# kfly_v3_1.net
KiCad netlist of a schematic drawn in EAGLE
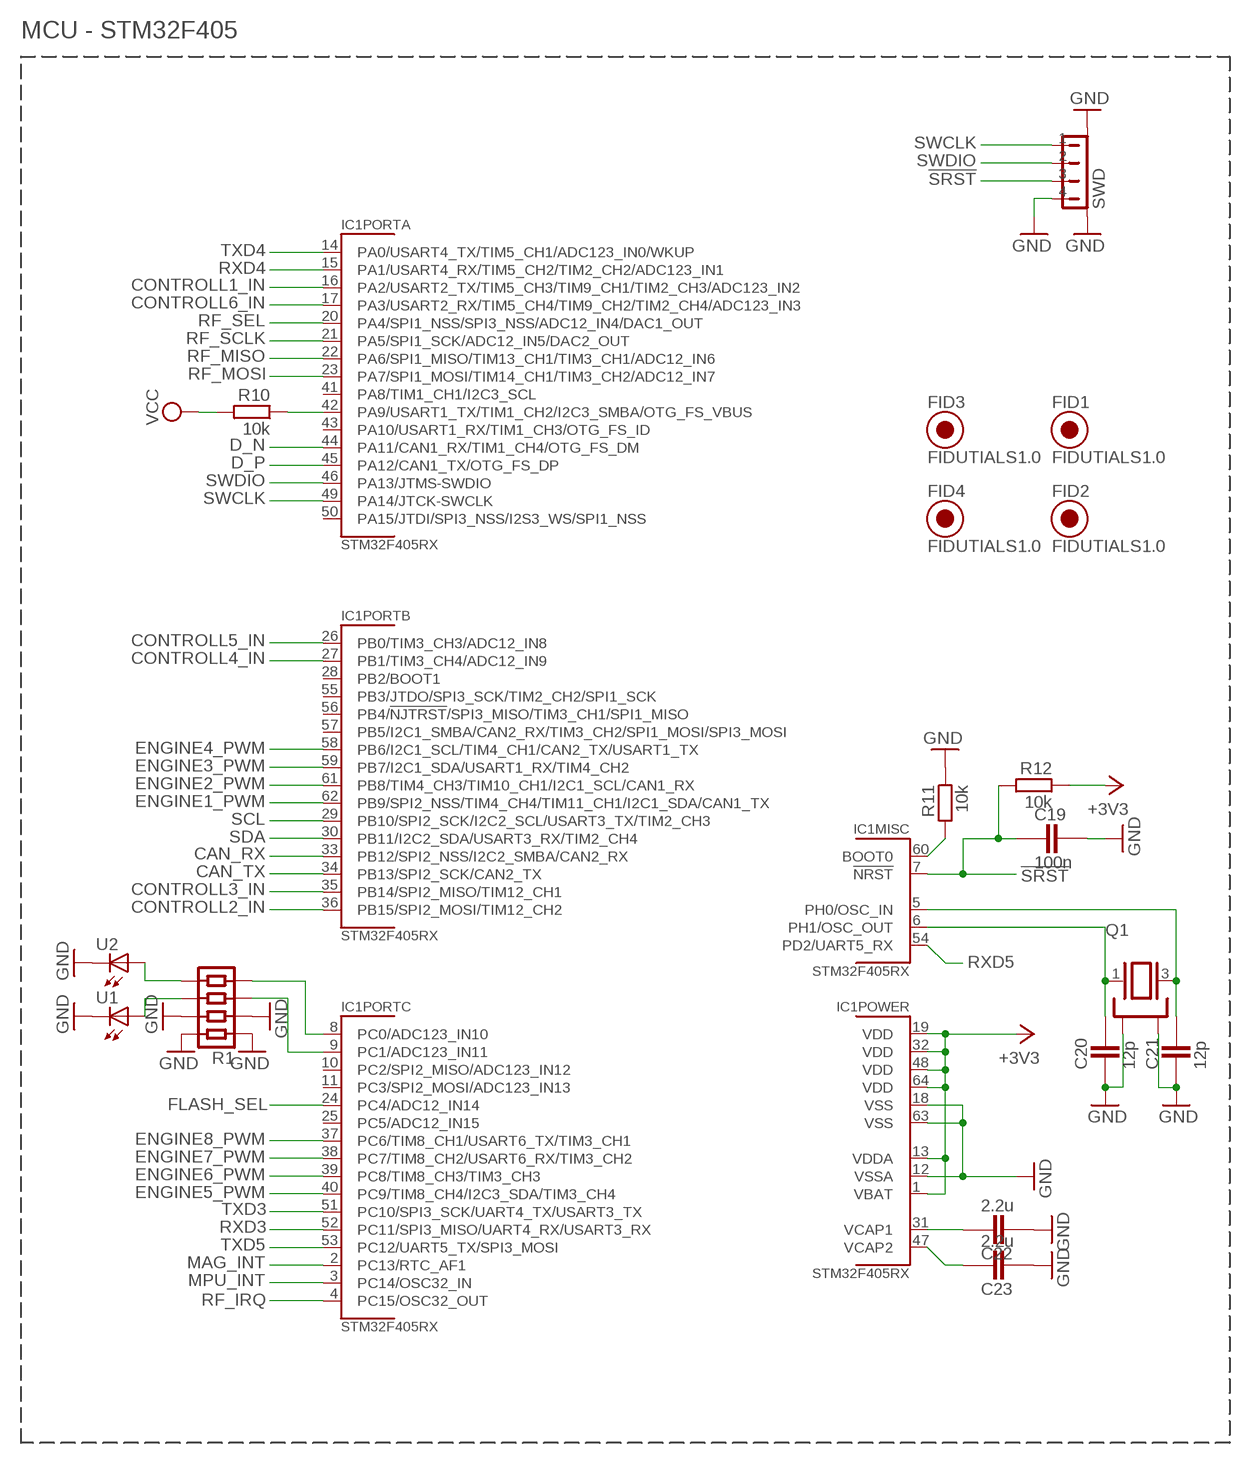
[diagram p0: schematic, sheet 1]
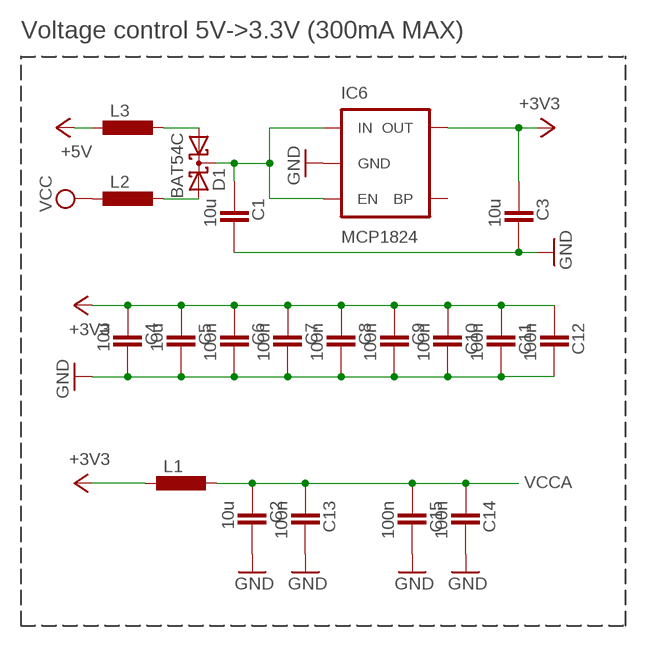
[diagram p1: schematic, sheet 2]
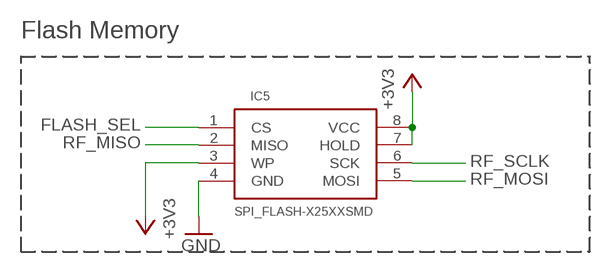
[diagram p2: schematic, sheet 3]
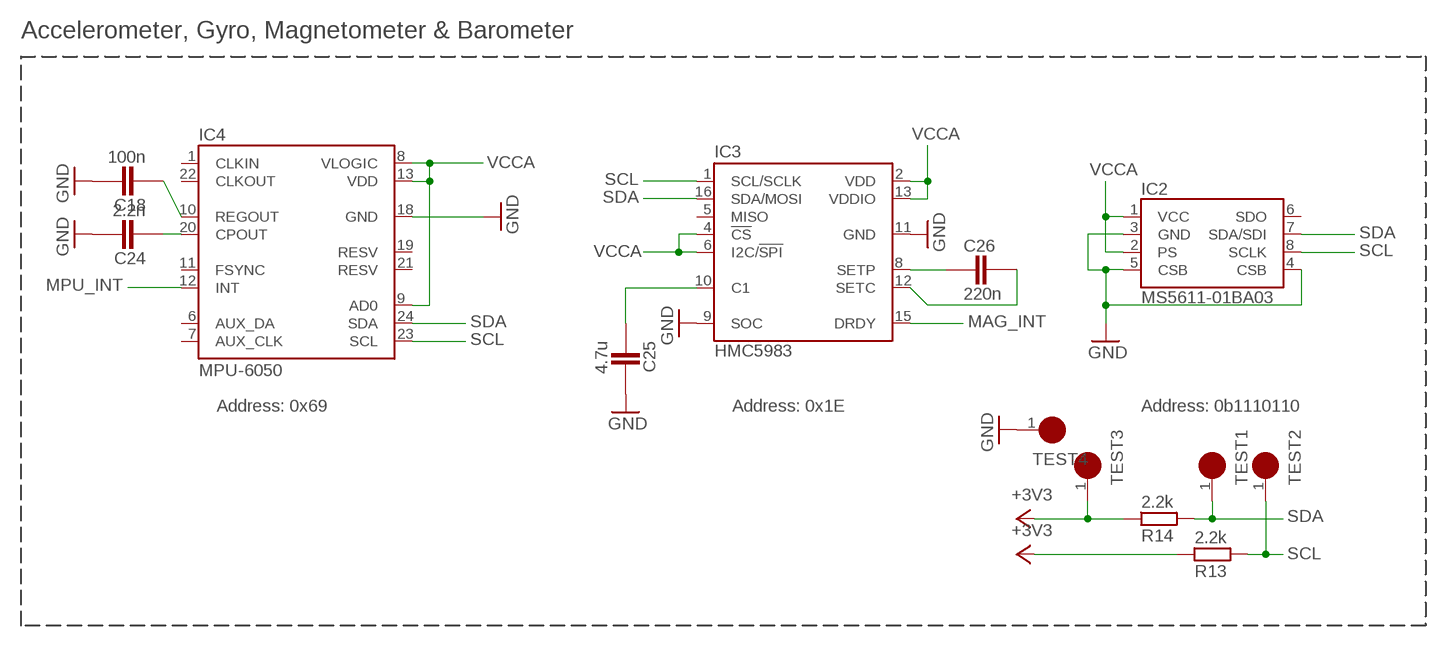
[diagram p3: schematic, sheet 4]
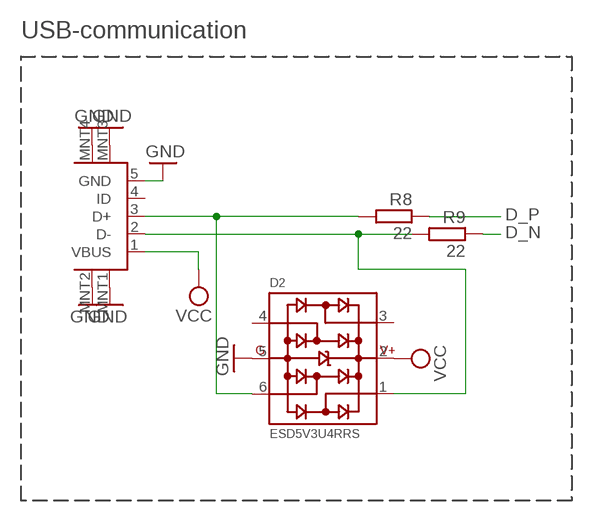
[diagram p4: schematic, sheet 5]
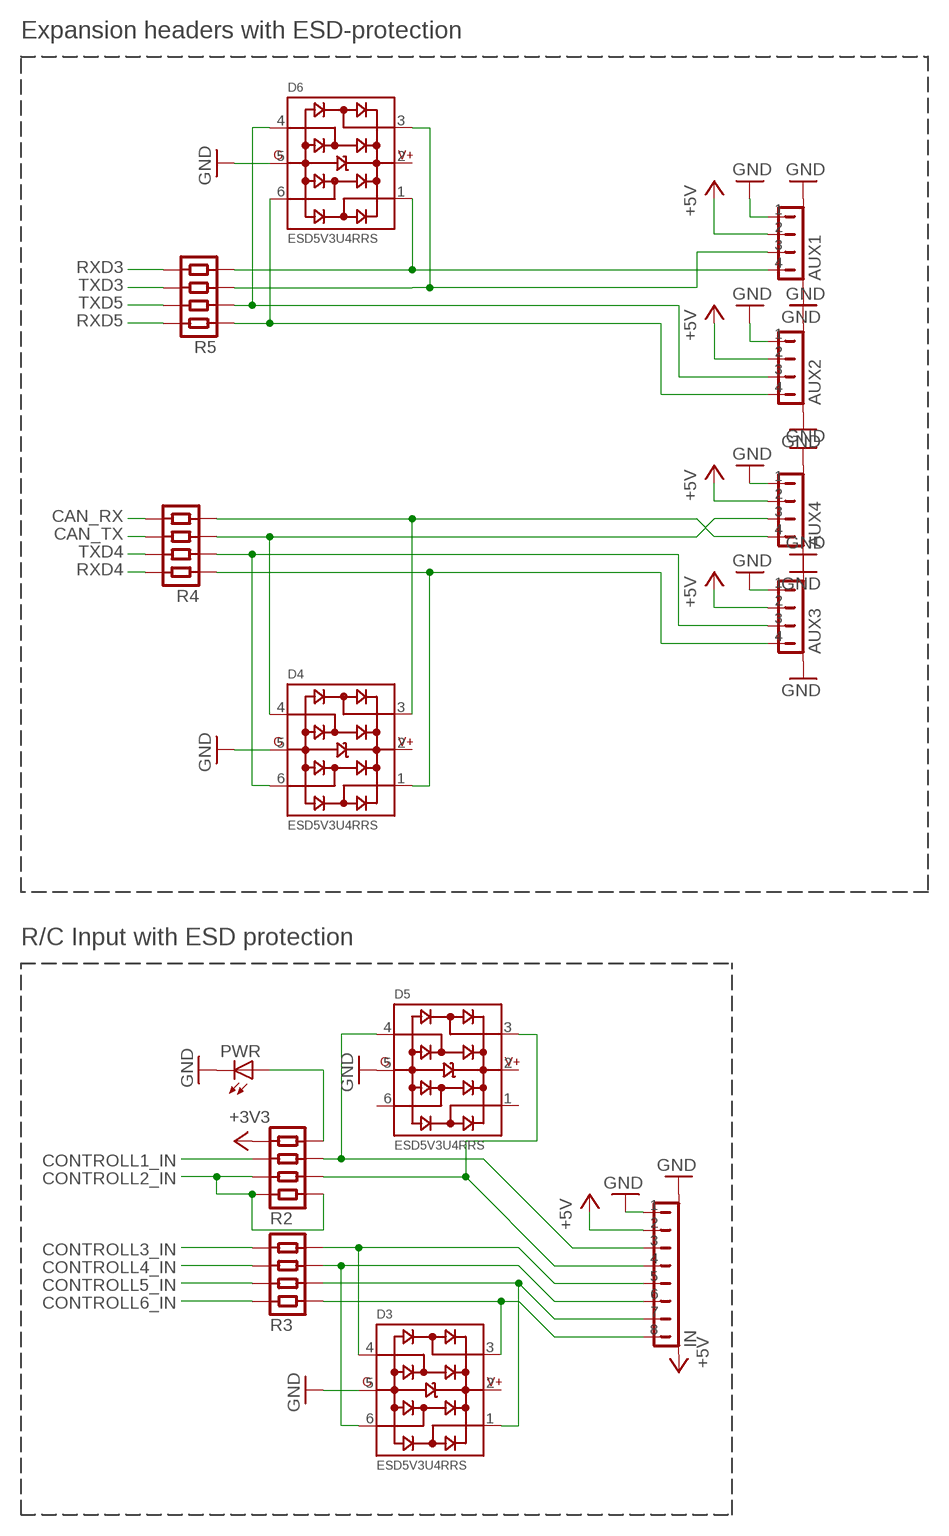
[diagram p5: schematic, sheet 6]
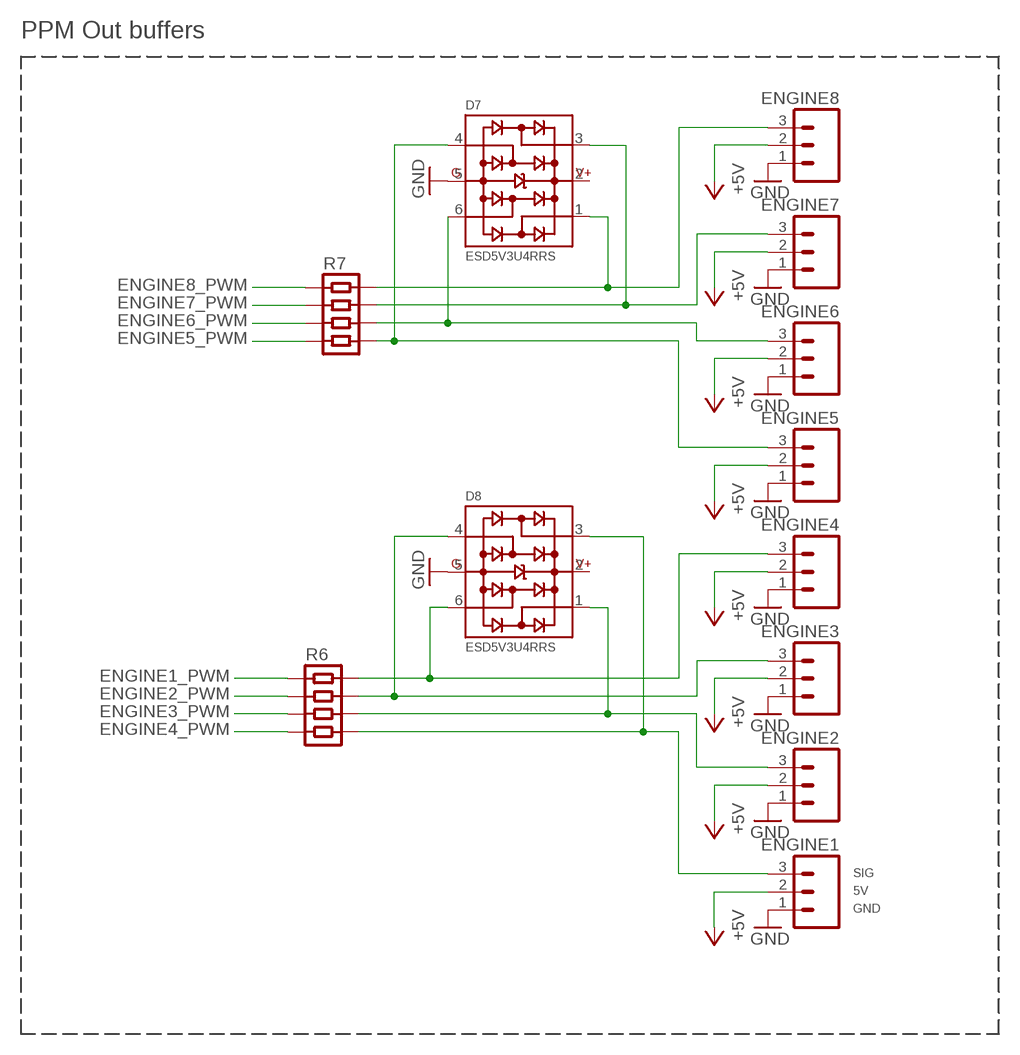
[diagram p6: schematic, sheet 7]
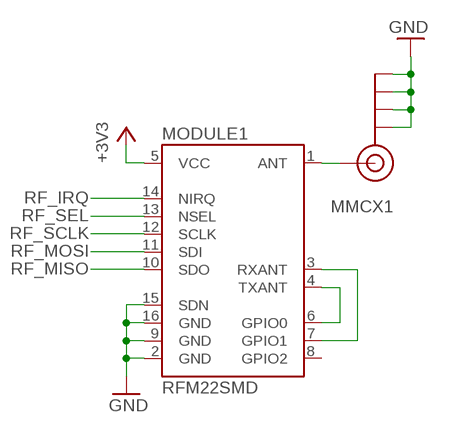
[diagram p7: schematic, sheet 8]

(export (version "E")
  (design (tool "Eeschema 10.0.6"))
  (components
    (comp (ref "C1")
      (value "10u")
      (footprint "eagle-import:CAPC1608X92N")
      (libsource (lib "eagle-import") (part "CAPACITOR_0603"))
    )
    (comp (ref "C2")
      (value "10u")
      (footprint "eagle-import:CAPC1608X92N")
      (libsource (lib "eagle-import") (part "CAPACITOR_0603"))
    )
    (comp (ref "C3")
      (value "10u")
      (footprint "eagle-import:CAPC1608X92N")
      (libsource (lib "eagle-import") (part "CAPACITOR_0603"))
    )
    (comp (ref "C4")
      (value "10u")
      (footprint "eagle-import:CAPC1608X92N")
      (libsource (lib "eagle-import") (part "CAPACITOR_0603"))
    )
    (comp (ref "C5")
      (value "10u")
      (footprint "eagle-import:CAPC1608X92N")
      (libsource (lib "eagle-import") (part "CAPACITOR_0603"))
    )
    (comp (ref "C6")
      (value "100n")
      (footprint "eagle-import:CAPC1005X60N")
      (libsource (lib "eagle-import") (part "CAPACITOR_0402"))
    )
    (comp (ref "C7")
      (value "100n")
      (footprint "eagle-import:CAPC1005X60N")
      (libsource (lib "eagle-import") (part "CAPACITOR_0402"))
    )
    (comp (ref "C8")
      (value "100n")
      (footprint "eagle-import:CAPC1005X60N")
      (libsource (lib "eagle-import") (part "CAPACITOR_0402"))
    )
    (comp (ref "C9")
      (value "100n")
      (footprint "eagle-import:CAPC1005X60N")
      (libsource (lib "eagle-import") (part "CAPACITOR_0402"))
    )
    (comp (ref "C10")
      (value "100n")
      (footprint "eagle-import:CAPC1005X60N")
      (libsource (lib "eagle-import") (part "CAPACITOR_0402"))
    )
    (comp (ref "C11")
      (value "100n")
      (footprint "eagle-import:CAPC1005X60N")
      (libsource (lib "eagle-import") (part "CAPACITOR_0402"))
    )
    (comp (ref "C12")
      (value "100n")
      (footprint "eagle-import:CAPC1005X60N")
      (libsource (lib "eagle-import") (part "CAPACITOR_0402"))
    )
    (comp (ref "C13")
      (value "100n")
      (footprint "eagle-import:CAPC1005X60N")
      (libsource (lib "eagle-import") (part "CAPACITOR_0402"))
    )
    (comp (ref "C14")
      (value "100n")
      (footprint "eagle-import:CAPC1005X60N")
      (libsource (lib "eagle-import") (part "CAPACITOR_0402"))
    )
    (comp (ref "C15")
      (value "100n")
      (footprint "eagle-import:CAPC1005X60N")
      (libsource (lib "eagle-import") (part "CAPACITOR_0402"))
    )
    (comp (ref "D1")
      (value "BAT54C")
      (footprint "eagle-import:SOT23")
      (libsource (lib "eagle-import") (part "BAT54C"))
    )
    (comp (ref "IC6")
      (value "MCP1824")
      (footprint "eagle-import:SOT23-5")
      (libsource (lib "eagle-import") (part "V_REG_LDOSMD"))
    )
    (comp (ref "L1")
      (value "INDUCTOR_0603")
      (footprint "eagle-import:INDC1608X95N")
      (libsource (lib "eagle-import") (part "INDUCTOR_0603"))
    )
    (comp (ref "L2")
      (value "INDUCTOR_0603")
      (footprint "eagle-import:INDC1608X95N")
      (libsource (lib "eagle-import") (part "INDUCTOR_0603"))
    )
    (comp (ref "L3")
      (value "INDUCTOR_0603")
      (footprint "eagle-import:INDC1608X95N")
      (libsource (lib "eagle-import") (part "INDUCTOR_0603"))
    )
    (comp (ref "C18")
      (value "100n")
      (footprint "eagle-import:CAPC1005X60N")
      (libsource (lib "eagle-import") (part "CAPACITOR_0402"))
    )
    (comp (ref "C24")
      (value "2.2n")
      (footprint "eagle-import:CAPC1005X60N")
      (libsource (lib "eagle-import") (part "CAPACITOR_0402"))
    )
    (comp (ref "C25")
      (value "4.7u")
      (footprint "eagle-import:CAPC1608X92N")
      (libsource (lib "eagle-import") (part "CAPACITOR_0603"))
    )
    (comp (ref "C26")
      (value "220n")
      (footprint "eagle-import:CAPC1608X92N")
      (libsource (lib "eagle-import") (part "CAPACITOR_0603"))
    )
    (comp (ref "IC2")
      (value "MS5611-01BA03")
      (footprint "eagle-import:MS5611")
      (libsource (lib "eagle-import") (part "MS5611-01BA01"))
    )
    (comp (ref "IC3")
      (value "HMC5983")
      (footprint "eagle-import:LPCC16")
      (libsource (lib "eagle-import") (part "HMC5983"))
    )
    (comp (ref "IC4")
      (value "MPU-6050")
      (footprint "eagle-import:QFN-24")
      (libsource (lib "eagle-import") (part "MPU-6050"))
    )
    (comp (ref "R13")
      (value "2.2k")
      (footprint "eagle-import:RESC1005X40AN")
      (libsource (lib "eagle-import") (part "RESISTOR_0402"))
    )
    (comp (ref "R14")
      (value "2.2k")
      (footprint "eagle-import:RESC1005X40AN")
      (libsource (lib "eagle-import") (part "RESISTOR_0402"))
    )
    (comp (ref "TEST1")
      (value "TESTPOINT")
      (footprint "eagle-import:TESTPOINT_1.2")
      (libsource (lib "eagle-import") (part "TESTPOINT"))
    )
    (comp (ref "TEST2")
      (value "TESTPOINT")
      (footprint "eagle-import:TESTPOINT_1.2")
      (libsource (lib "eagle-import") (part "TESTPOINT"))
    )
    (comp (ref "TEST3")
      (value "TESTPOINT")
      (footprint "eagle-import:TESTPOINT_1.2")
      (libsource (lib "eagle-import") (part "TESTPOINT"))
    )
    (comp (ref "TEST4")
      (value "TESTPOINT")
      (footprint "eagle-import:TESTPOINT_1.2")
      (libsource (lib "eagle-import") (part "TESTPOINT"))
    )
    (comp (ref "D7")
      (value "ESD5V3U4RRS")
      (footprint "eagle-import:SOT363")
      (libsource (lib "eagle-import") (part "ESD5V3U4RRS"))
    )
    (comp (ref "D8")
      (value "ESD5V3U4RRS")
      (footprint "eagle-import:SOT363")
      (libsource (lib "eagle-import") (part "ESD5V3U4RRS"))
    )
    (comp (ref "ENGINE1")
      (value "M03TH_90DEG")
      (footprint "eagle-import:M03_90DEG")
      (libsource (lib "eagle-import") (part "M03TH_90DEG"))
    )
    (comp (ref "ENGINE2")
      (value "M03TH_90DEG")
      (footprint "eagle-import:M03_90DEG")
      (libsource (lib "eagle-import") (part "M03TH_90DEG"))
    )
    (comp (ref "ENGINE3")
      (value "M03TH_90DEG")
      (footprint "eagle-import:M03_90DEG")
      (libsource (lib "eagle-import") (part "M03TH_90DEG"))
    )
    (comp (ref "ENGINE4")
      (value "M03TH_90DEG")
      (footprint "eagle-import:M03_90DEG")
      (libsource (lib "eagle-import") (part "M03TH_90DEG"))
    )
    (comp (ref "ENGINE5")
      (value "M03TH_90DEG")
      (footprint "eagle-import:M03_90DEG")
      (libsource (lib "eagle-import") (part "M03TH_90DEG"))
    )
    (comp (ref "ENGINE6")
      (value "M03TH_90DEG")
      (footprint "eagle-import:M03_90DEG")
      (libsource (lib "eagle-import") (part "M03TH_90DEG"))
    )
    (comp (ref "ENGINE7")
      (value "M03TH_90DEG")
      (footprint "eagle-import:M03_90DEG")
      (libsource (lib "eagle-import") (part "M03TH_90DEG"))
    )
    (comp (ref "ENGINE8")
      (value "M03TH_90DEG")
      (footprint "eagle-import:M03_90DEG")
      (libsource (lib "eagle-import") (part "M03TH_90DEG"))
    )
    (comp (ref "R6")
      (value "RESISTOR-4ARRAY-0804")
      (footprint "eagle-import:RESISTORARRAY_0804")
      (libsource (lib "eagle-import") (part "RESISTOR-4ARRAY-0804"))
    )
    (comp (ref "R7")
      (value "RESISTOR-4ARRAY-0804")
      (footprint "eagle-import:RESISTORARRAY_0804")
      (libsource (lib "eagle-import") (part "RESISTOR-4ARRAY-0804"))
    )
    (comp (ref "C19")
      (value "100n")
      (footprint "eagle-import:CAPC1005X60N")
      (libsource (lib "eagle-import") (part "CAPACITOR_0402"))
    )
    (comp (ref "C20")
      (value "12p")
      (footprint "eagle-import:CAPC1005X60N")
      (libsource (lib "eagle-import") (part "CAPACITOR_0402"))
    )
    (comp (ref "C21")
      (value "12p")
      (footprint "eagle-import:CAPC1005X60N")
      (libsource (lib "eagle-import") (part "CAPACITOR_0402"))
    )
    (comp (ref "C22")
      (value "2.2u")
      (footprint "eagle-import:CAPC1608X92N")
      (libsource (lib "eagle-import") (part "CAPACITOR_0603"))
    )
    (comp (ref "C23")
      (value "2.2u")
      (footprint "eagle-import:CAPC1608X92N")
      (libsource (lib "eagle-import") (part "CAPACITOR_0603"))
    )
    (comp (ref "FID1")
      (value "FIDUTIALS1.0")
      (footprint "eagle-import:FID1.0")
      (libsource (lib "eagle-import") (part "FIDUTIALS1.0"))
    )
    (comp (ref "FID2")
      (value "FIDUTIALS1.0")
      (footprint "eagle-import:FID1.0")
      (libsource (lib "eagle-import") (part "FIDUTIALS1.0"))
    )
    (comp (ref "FID3")
      (value "FIDUTIALS1.0")
      (footprint "eagle-import:FID1.0")
      (libsource (lib "eagle-import") (part "FIDUTIALS1.0"))
    )
    (comp (ref "FID4")
      (value "FIDUTIALS1.0")
      (footprint "eagle-import:FID1.0")
      (libsource (lib "eagle-import") (part "FIDUTIALS1.0"))
    )
    (comp (ref "IC1")
      (value "STM32F405RX")
      (footprint "eagle-import:LQFP64-10X10")
      (libsource (lib "eagle-import") (part "STM32F4X5RX"))
    )
    (comp (ref "Q1")
      (value "2.5X3.2CRYSTAL")
      (footprint "eagle-import:2.5X3.2CRYSTAL")
      (libsource (lib "eagle-import") (part "2.5X3.2CRYSTAL"))
    )
    (comp (ref "R1")
      (value "RESISTOR-4ARRAY-0804")
      (footprint "eagle-import:RESISTORARRAY_0804")
      (libsource (lib "eagle-import") (part "RESISTOR-4ARRAY-0804"))
    )
    (comp (ref "R10")
      (value "10k")
      (footprint "eagle-import:RESC1005X40AN")
      (libsource (lib "eagle-import") (part "RESISTOR_0402"))
    )
    (comp (ref "R11")
      (value "10k")
      (footprint "eagle-import:RESC1005X40AN")
      (libsource (lib "eagle-import") (part "RESISTOR_0402"))
    )
    (comp (ref "R12")
      (value "10k")
      (footprint "eagle-import:RESC1005X40AN")
      (libsource (lib "eagle-import") (part "RESISTOR_0402"))
    )
    (comp (ref "SWD")
      (value "JST-4PIN-SIDE-1.0")
      (footprint "eagle-import:JST-4PIN-SIDE")
      (libsource (lib "eagle-import") (part "JST-4PIN-SIDE-1.0"))
    )
    (comp (ref "U1")
      (value "LED0603")
      (footprint "eagle-import:LED-0603")
      (libsource (lib "eagle-import") (part "LED0603"))
    )
    (comp (ref "U2")
      (value "LED0603")
      (footprint "eagle-import:LED-0603")
      (libsource (lib "eagle-import") (part "LED0603"))
    )
    (comp (ref "AUX1")
      (value "JST-4PIN-SIDE-1.0")
      (footprint "eagle-import:JST-4PIN-SIDE")
      (libsource (lib "eagle-import") (part "JST-4PIN-SIDE-1.0"))
    )
    (comp (ref "AUX2")
      (value "JST-4PIN-SIDE-1.0")
      (footprint "eagle-import:JST-4PIN-SIDE")
      (libsource (lib "eagle-import") (part "JST-4PIN-SIDE-1.0"))
    )
    (comp (ref "AUX3")
      (value "JST-4PIN-SIDE-1.0")
      (footprint "eagle-import:JST-4PIN-SIDE")
      (libsource (lib "eagle-import") (part "JST-4PIN-SIDE-1.0"))
    )
    (comp (ref "AUX4")
      (value "JST-4PIN-SIDE-1.0")
      (footprint "eagle-import:JST-4PIN-SIDE")
      (libsource (lib "eagle-import") (part "JST-4PIN-SIDE-1.0"))
    )
    (comp (ref "D3")
      (value "ESD5V3U4RRS")
      (footprint "eagle-import:SOT363")
      (libsource (lib "eagle-import") (part "ESD5V3U4RRS"))
    )
    (comp (ref "D4")
      (value "ESD5V3U4RRS")
      (footprint "eagle-import:SOT363")
      (libsource (lib "eagle-import") (part "ESD5V3U4RRS"))
    )
    (comp (ref "D5")
      (value "ESD5V3U4RRS")
      (footprint "eagle-import:SOT363")
      (libsource (lib "eagle-import") (part "ESD5V3U4RRS"))
    )
    (comp (ref "D6")
      (value "ESD5V3U4RRS")
      (footprint "eagle-import:SOT363")
      (libsource (lib "eagle-import") (part "ESD5V3U4RRS"))
    )
    (comp (ref "IN")
      (value "JST-8PIN-SIDE-1.0")
      (footprint "eagle-import:JST-8PIN-SIDE")
      (libsource (lib "eagle-import") (part "JST-8PIN-SIDE-1.0"))
    )
    (comp (ref "PWR")
      (value "LED0603")
      (footprint "eagle-import:LED-0603")
      (libsource (lib "eagle-import") (part "LED0603"))
    )
    (comp (ref "R2")
      (value "RESISTOR-4ARRAY-0804")
      (footprint "eagle-import:RESISTORARRAY_0804")
      (libsource (lib "eagle-import") (part "RESISTOR-4ARRAY-0804"))
    )
    (comp (ref "R3")
      (value "RESISTOR-4ARRAY-0804")
      (footprint "eagle-import:RESISTORARRAY_0804")
      (libsource (lib "eagle-import") (part "RESISTOR-4ARRAY-0804"))
    )
    (comp (ref "R4")
      (value "RESISTOR-4ARRAY-0804")
      (footprint "eagle-import:RESISTORARRAY_0804")
      (libsource (lib "eagle-import") (part "RESISTOR-4ARRAY-0804"))
    )
    (comp (ref "R5")
      (value "RESISTOR-4ARRAY-0804")
      (footprint "eagle-import:RESISTORARRAY_0804")
      (libsource (lib "eagle-import") (part "RESISTOR-4ARRAY-0804"))
    )
    (comp (ref "IC5")
      (value "SPI_FLASH-X25XXSMD")
      (footprint "eagle-import:SO08")
      (libsource (lib "eagle-import") (part "SPI_FLASH-X25XXSMD"))
    )
    (comp (ref "D2")
      (value "ESD5V3U4RRS")
      (footprint "eagle-import:SOT363")
      (libsource (lib "eagle-import") (part "ESD5V3U4RRS"))
    )
    (comp (ref "R8")
      (value "22")
      (footprint "eagle-import:RESC1005X40AN")
      (libsource (lib "eagle-import") (part "RESISTOR_0402"))
    )
    (comp (ref "R9")
      (value "22")
      (footprint "eagle-import:RESC1005X40AN")
      (libsource (lib "eagle-import") (part "RESISTOR_0402"))
    )
    (comp (ref "USB1")
      (value "USB-MICRO-B-BOTTOM")
      (footprint "eagle-import:MICROUSB_TYPEB_SURFACE")
      (libsource (lib "eagle-import") (part "USB-MICRO-B-BOTTOM"))
    )
    (comp (ref "MMCX1")
      (value "MMCX")
      (footprint "eagle-import:MMCX_THROUGHHOLE_RIGHTANGLE")
      (libsource (lib "eagle-import") (part "MMCX"))
    )
    (comp (ref "MODULE1")
      (value "RFM22SMD")
      (footprint "eagle-import:RFM22-XXX-S2")
      (libsource (lib "eagle-import") (part "RFM22SMD"))
    )
  )
  (nets
    (net (code "1") (name "+3V3") (class "Default")
      (node (ref "C10") (pin "1") (pinfunction "1_1") (pintype "passive"))
      (node (ref "C11") (pin "1") (pinfunction "1_1") (pintype "passive"))
      (node (ref "C12") (pin "1") (pinfunction "1_1") (pintype "passive"))
      (node (ref "C3") (pin "1") (pinfunction "1_1") (pintype "passive"))
      (node (ref "C4") (pin "1") (pinfunction "1_1") (pintype "passive"))
      (node (ref "C5") (pin "1") (pinfunction "1_1") (pintype "passive"))
      (node (ref "C6") (pin "1") (pinfunction "1_1") (pintype "passive"))
      (node (ref "C7") (pin "1") (pinfunction "1_1") (pintype "passive"))
      (node (ref "C8") (pin "1") (pinfunction "1_1") (pintype "passive"))
      (node (ref "C9") (pin "1") (pinfunction "1_1") (pintype "passive"))
      (node (ref "IC1") (pin "1") (pinfunction "VBAT_1") (pintype "bidirectional"))
      (node (ref "IC1") (pin "13") (pinfunction "VDDA_13") (pintype "bidirectional"))
      (node (ref "IC1") (pin "19") (pinfunction "VDD_19") (pintype "bidirectional"))
      (node (ref "IC1") (pin "32") (pinfunction "VDD_32") (pintype "bidirectional"))
      (node (ref "IC1") (pin "48") (pinfunction "VDD_48") (pintype "bidirectional"))
      (node (ref "IC1") (pin "64") (pinfunction "VDD_64") (pintype "bidirectional"))
      (node (ref "IC5") (pin "3") (pinfunction "WP_3") (pintype "bidirectional"))
      (node (ref "IC5") (pin "7") (pinfunction "HOLD_7") (pintype "bidirectional"))
      (node (ref "IC5") (pin "8") (pinfunction "VCC_8") (pintype "bidirectional"))
      (node (ref "IC6") (pin "5") (pinfunction "OUT_5") (pintype "passive"))
      (node (ref "L1") (pin "1") (pinfunction "1_1") (pintype "passive"))
      (node (ref "MODULE1") (pin "5") (pinfunction "VCC_5") (pintype "bidirectional"))
      (node (ref "R12") (pin "1") (pinfunction "1_1") (pintype "passive"))
      (node (ref "R13") (pin "1") (pinfunction "1_1") (pintype "passive"))
      (node (ref "R14") (pin "1") (pinfunction "1_1") (pintype "passive"))
      (node (ref "R2") (pin "4") (pinfunction "4_4") (pintype "bidirectional"))
      (node (ref "TEST3") (pin "1") (pinfunction "2_1") (pintype "passive"))
    )
    (net (code "2") (name "+5V") (class "Default")
      (node (ref "AUX1") (pin "2") (pinfunction "2_2") (pintype "bidirectional"))
      (node (ref "AUX2") (pin "2") (pinfunction "2_2") (pintype "bidirectional"))
      (node (ref "AUX3") (pin "2") (pinfunction "2_2") (pintype "bidirectional"))
      (node (ref "AUX4") (pin "2") (pinfunction "2_2") (pintype "bidirectional"))
      (node (ref "ENGINE1") (pin "2") (pinfunction "2_2") (pintype "passive"))
      (node (ref "ENGINE2") (pin "2") (pinfunction "2_2") (pintype "passive"))
      (node (ref "ENGINE3") (pin "2") (pinfunction "2_2") (pintype "passive"))
      (node (ref "ENGINE4") (pin "2") (pinfunction "2_2") (pintype "passive"))
      (node (ref "ENGINE5") (pin "2") (pinfunction "2_2") (pintype "passive"))
      (node (ref "ENGINE6") (pin "2") (pinfunction "2_2") (pintype "passive"))
      (node (ref "ENGINE7") (pin "2") (pinfunction "2_2") (pintype "passive"))
      (node (ref "ENGINE8") (pin "2") (pinfunction "2_2") (pintype "passive"))
      (node (ref "IN") (pin "2") (pinfunction "2_2") (pintype "bidirectional"))
      (node (ref "IN") (pin "NC2") (pinfunction "GND2_NC2") (pintype "bidirectional"))
      (node (ref "L3") (pin "1") (pinfunction "1_1") (pintype "passive"))
    )
    (net (code "3") (name "CAN_RX") (class "Default")
      (node (ref "IC1") (pin "33") (pinfunction "PB12/SPI2_NSS/I2C2_SMBA/CAN2_RX_33") (pintype "bidirectional"))
      (node (ref "R4") (pin "5") (pinfunction "5_5") (pintype "bidirectional"))
    )
    (net (code "4") (name "CAN_TX") (class "Default")
      (node (ref "IC1") (pin "34") (pinfunction "PB13/SPI2_SCK/CAN2_TX_34") (pintype "bidirectional"))
      (node (ref "R4") (pin "6") (pinfunction "6_6") (pintype "bidirectional"))
    )
    (net (code "5") (name "CONTROLL1_IN") (class "Default")
      (node (ref "IC1") (pin "16") (pinfunction "PA2/USART2_TX/TIM5_CH3/TIM9_CH1/TIM2_CH3/ADC123_IN2_16") (pintype "bidirectional"))
      (node (ref "R2") (pin "3") (pinfunction "3_3") (pintype "bidirectional"))
    )
    (net (code "6") (name "CONTROLL2_IN") (class "Default")
      (node (ref "IC1") (pin "36") (pinfunction "PB15/SPI2_MOSI/TIM12_CH2_36") (pintype "bidirectional"))
      (node (ref "R2") (pin "1") (pinfunction "1_1") (pintype "bidirectional"))
      (node (ref "R2") (pin "2") (pinfunction "2_2") (pintype "bidirectional"))
      (node (ref "R2") (pin "8") (pinfunction "8_8") (pintype "bidirectional"))
    )
    (net (code "7") (name "CONTROLL3_IN") (class "Default")
      (node (ref "IC1") (pin "35") (pinfunction "PB14/SPI2_MISO/TIM12_CH1_35") (pintype "bidirectional"))
      (node (ref "R3") (pin "4") (pinfunction "4_4") (pintype "bidirectional"))
    )
    (net (code "8") (name "CONTROLL4_IN") (class "Default")
      (node (ref "IC1") (pin "27") (pinfunction "PB1/TIM3_CH4/ADC12_IN9_27") (pintype "bidirectional"))
      (node (ref "R3") (pin "3") (pinfunction "3_3") (pintype "bidirectional"))
    )
    (net (code "9") (name "CONTROLL5_IN") (class "Default")
      (node (ref "IC1") (pin "26") (pinfunction "PB0/TIM3_CH3/ADC12_IN8_26") (pintype "bidirectional"))
      (node (ref "R3") (pin "2") (pinfunction "2_2") (pintype "bidirectional"))
    )
    (net (code "10") (name "CONTROLL6_IN") (class "Default")
      (node (ref "IC1") (pin "17") (pinfunction "PA3/USART2_RX/TIM5_CH4/TIM9_CH2/TIM2_CH4/ADC123_IN3_17") (pintype "bidirectional"))
      (node (ref "R3") (pin "1") (pinfunction "1_1") (pintype "bidirectional"))
    )
    (net (code "11") (name "D_N") (class "Default")
      (node (ref "IC1") (pin "44") (pinfunction "PA11/CAN1_RX/TIM1_CH4/OTG_FS_DM_44") (pintype "bidirectional"))
      (node (ref "R9") (pin "1") (pinfunction "1_1") (pintype "passive"))
    )
    (net (code "12") (name "D_P") (class "Default")
      (node (ref "IC1") (pin "45") (pinfunction "PA12/CAN1_TX/OTG_FS_DP_45") (pintype "bidirectional"))
      (node (ref "R8") (pin "1") (pinfunction "1_1") (pintype "passive"))
    )
    (net (code "13") (name "ENGINE1_PWM") (class "Default")
      (node (ref "IC1") (pin "62") (pinfunction "PB9/SPI2_NSS/TIM4_CH4/TIM11_CH1/I2C1_SDA/CAN1_TX_62") (pintype "bidirectional"))
      (node (ref "R6") (pin "1") (pinfunction "1_1") (pintype "bidirectional"))
    )
    (net (code "14") (name "ENGINE2_PWM") (class "Default")
      (node (ref "IC1") (pin "61") (pinfunction "PB8/TIM4_CH3/TIM10_CH1/I2C1_SCL/CAN1_RX_61") (pintype "bidirectional"))
      (node (ref "R6") (pin "2") (pinfunction "2_2") (pintype "bidirectional"))
    )
    (net (code "15") (name "ENGINE3_PWM") (class "Default")
      (node (ref "IC1") (pin "59") (pinfunction "PB7/I2C1_SDA/USART1_RX/TIM4_CH2_59") (pintype "bidirectional"))
      (node (ref "R6") (pin "3") (pinfunction "3_3") (pintype "bidirectional"))
    )
    (net (code "16") (name "ENGINE4_PWM") (class "Default")
      (node (ref "IC1") (pin "58") (pinfunction "PB6/I2C1_SCL/TIM4_CH1/CAN2_TX/USART1_TX_58") (pintype "bidirectional"))
      (node (ref "R6") (pin "4") (pinfunction "4_4") (pintype "bidirectional"))
    )
    (net (code "17") (name "ENGINE5_PWM") (class "Default")
      (node (ref "IC1") (pin "40") (pinfunction "PC9/TIM8_CH4/I2C3_SDA/TIM3_CH4_40") (pintype "bidirectional"))
      (node (ref "R7") (pin "4") (pinfunction "4_4") (pintype "bidirectional"))
    )
    (net (code "18") (name "ENGINE6_PWM") (class "Default")
      (node (ref "IC1") (pin "39") (pinfunction "PC8/TIM8_CH3/TIM3_CH3_39") (pintype "bidirectional"))
      (node (ref "R7") (pin "3") (pinfunction "3_3") (pintype "bidirectional"))
    )
    (net (code "19") (name "ENGINE7_PWM") (class "Default")
      (node (ref "IC1") (pin "38") (pinfunction "PC7/TIM8_CH2/USART6_RX/TIM3_CH2_38") (pintype "bidirectional"))
      (node (ref "R7") (pin "2") (pinfunction "2_2") (pintype "bidirectional"))
    )
    (net (code "20") (name "ENGINE8_PWM") (class "Default")
      (node (ref "IC1") (pin "37") (pinfunction "PC6/TIM8_CH1/USART6_TX/TIM3_CH1_37") (pintype "bidirectional"))
      (node (ref "R7") (pin "1") (pinfunction "1_1") (pintype "bidirectional"))
    )
    (net (code "21") (name "FLASH_SEL") (class "Default")
      (node (ref "IC1") (pin "24") (pinfunction "PC4/ADC12_IN14_24") (pintype "bidirectional"))
      (node (ref "IC5") (pin "1") (pinfunction "CS_1") (pintype "bidirectional"))
    )
    (net (code "22") (name "GND") (class "Default")
      (node (ref "AUX1") (pin "1") (pinfunction "1_1") (pintype "bidirectional"))
      (node (ref "AUX1") (pin "NC1") (pinfunction "P1_NC1") (pintype "bidirectional"))
      (node (ref "AUX1") (pin "NC2") (pinfunction "P2_NC2") (pintype "bidirectional"))
      (node (ref "AUX2") (pin "1") (pinfunction "1_1") (pintype "bidirectional"))
      (node (ref "AUX2") (pin "NC1") (pinfunction "P1_NC1") (pintype "bidirectional"))
      (node (ref "AUX2") (pin "NC2") (pinfunction "P2_NC2") (pintype "bidirectional"))
      (node (ref "AUX3") (pin "1") (pinfunction "1_1") (pintype "bidirectional"))
      (node (ref "AUX3") (pin "NC1") (pinfunction "P1_NC1") (pintype "bidirectional"))
      (node (ref "AUX3") (pin "NC2") (pinfunction "P2_NC2") (pintype "bidirectional"))
      (node (ref "AUX4") (pin "1") (pinfunction "1_1") (pintype "bidirectional"))
      (node (ref "AUX4") (pin "NC1") (pinfunction "P1_NC1") (pintype "bidirectional"))
      (node (ref "AUX4") (pin "NC2") (pinfunction "P2_NC2") (pintype "bidirectional"))
      (node (ref "C1") (pin "2") (pinfunction "2_2") (pintype "passive"))
      (node (ref "C10") (pin "2") (pinfunction "2_2") (pintype "passive"))
      (node (ref "C11") (pin "2") (pinfunction "2_2") (pintype "passive"))
      (node (ref "C12") (pin "2") (pinfunction "2_2") (pintype "passive"))
      (node (ref "C13") (pin "2") (pinfunction "2_2") (pintype "passive"))
      (node (ref "C14") (pin "2") (pinfunction "2_2") (pintype "passive"))
      (node (ref "C15") (pin "2") (pinfunction "2_2") (pintype "passive"))
      (node (ref "C18") (pin "2") (pinfunction "2_2") (pintype "passive"))
      (node (ref "C19") (pin "2") (pinfunction "2_2") (pintype "passive"))
      (node (ref "C2") (pin "2") (pinfunction "2_2") (pintype "passive"))
      (node (ref "C20") (pin "1") (pinfunction "1_1") (pintype "passive"))
      (node (ref "C21") (pin "1") (pinfunction "1_1") (pintype "passive"))
      (node (ref "C22") (pin "2") (pinfunction "2_2") (pintype "passive"))
      (node (ref "C23") (pin "2") (pinfunction "2_2") (pintype "passive"))
      (node (ref "C24") (pin "2") (pinfunction "2_2") (pintype "passive"))
      (node (ref "C25") (pin "2") (pinfunction "2_2") (pintype "passive"))
      (node (ref "C3") (pin "2") (pinfunction "2_2") (pintype "passive"))
      (node (ref "C4") (pin "2") (pinfunction "2_2") (pintype "passive"))
      (node (ref "C5") (pin "2") (pinfunction "2_2") (pintype "passive"))
      (node (ref "C6") (pin "2") (pinfunction "2_2") (pintype "passive"))
      (node (ref "C7") (pin "2") (pinfunction "2_2") (pintype "passive"))
      (node (ref "C8") (pin "2") (pinfunction "2_2") (pintype "passive"))
      (node (ref "C9") (pin "2") (pinfunction "2_2") (pintype "passive"))
      (node (ref "D2") (pin "5") (pinfunction "5_5") (pintype "bidirectional"))
      (node (ref "D3") (pin "5") (pinfunction "5_5") (pintype "bidirectional"))
      (node (ref "D4") (pin "5") (pinfunction "5_5") (pintype "bidirectional"))
      (node (ref "D5") (pin "5") (pinfunction "5_5") (pintype "bidirectional"))
      (node (ref "D6") (pin "5") (pinfunction "5_5") (pintype "bidirectional"))
      (node (ref "D7") (pin "5") (pinfunction "5_5") (pintype "bidirectional"))
      (node (ref "D8") (pin "5") (pinfunction "5_5") (pintype "bidirectional"))
      (node (ref "ENGINE1") (pin "1") (pinfunction "1_1") (pintype "passive"))
      (node (ref "ENGINE2") (pin "1") (pinfunction "1_1") (pintype "passive"))
      (node (ref "ENGINE3") (pin "1") (pinfunction "1_1") (pintype "passive"))
      (node (ref "ENGINE4") (pin "1") (pinfunction "1_1") (pintype "passive"))
      (node (ref "ENGINE5") (pin "1") (pinfunction "1_1") (pintype "passive"))
      (node (ref "ENGINE6") (pin "1") (pinfunction "1_1") (pintype "passive"))
      (node (ref "ENGINE7") (pin "1") (pinfunction "1_1") (pintype "passive"))
      (node (ref "ENGINE8") (pin "1") (pinfunction "1_1") (pintype "passive"))
      (node (ref "IC1") (pin "12") (pinfunction "VSSA_12") (pintype "bidirectional"))
      (node (ref "IC1") (pin "18") (pinfunction "VSS_18") (pintype "bidirectional"))
      (node (ref "IC1") (pin "63") (pinfunction "VSS_63") (pintype "bidirectional"))
      (node (ref "IC2") (pin "3") (pinfunction "GND_3") (pintype "bidirectional"))
      (node (ref "IC2") (pin "4") (pinfunction "CSB_4") (pintype "bidirectional"))
      (node (ref "IC2") (pin "5") (pinfunction "CSB_5") (pintype "bidirectional"))
      (node (ref "IC3") (pin "11") (pinfunction "GND_11") (pintype "bidirectional"))
      (node (ref "IC3") (pin "9") (pinfunction "SOC_9") (pintype "bidirectional"))
      (node (ref "IC4") (pin "18") (pinfunction "GND_18") (pintype "bidirectional"))
      (node (ref "IC5") (pin "4") (pinfunction "GND_4") (pintype "bidirectional"))
      (node (ref "IC6") (pin "2") (pinfunction "GND_2") (pintype "input"))
      (node (ref "IN") (pin "1") (pinfunction "1_1") (pintype "bidirectional"))
      (node (ref "IN") (pin "NC1") (pinfunction "GND1_NC1") (pintype "bidirectional"))
      (node (ref "MMCX1") (pin "G1") (pinfunction "GND_G1") (pintype "bidirectional"))
      (node (ref "MMCX1") (pin "G2") (pinfunction "GND_G2") (pintype "bidirectional"))
      (node (ref "MMCX1") (pin "G3") (pinfunction "GND_G3") (pintype "bidirectional"))
      (node (ref "MMCX1") (pin "G4") (pinfunction "GND_G4") (pintype "bidirectional"))
      (node (ref "MODULE1") (pin "15") (pinfunction "SDN_15") (pintype "input"))
      (node (ref "MODULE1") (pin "16") (pinfunction "GND_16") (pintype "power_in"))
      (node (ref "MODULE1") (pin "2") (pinfunction "GND_2") (pintype "power_in"))
      (node (ref "MODULE1") (pin "9") (pinfunction "GND_9") (pintype "power_in"))
      (node (ref "PWR") (pin "C") (pinfunction "C_C") (pintype "passive"))
      (node (ref "Q1") (pin "2") (pinfunction "P$1_2") (pintype "bidirectional"))
      (node (ref "Q1") (pin "4") (pinfunction "P$2_4") (pintype "bidirectional"))
      (node (ref "R1") (pin "1") (pinfunction "1_1") (pintype "bidirectional"))
      (node (ref "R1") (pin "2") (pinfunction "2_2") (pintype "bidirectional"))
      (node (ref "R1") (pin "7") (pinfunction "7_7") (pintype "bidirectional"))
      (node (ref "R1") (pin "8") (pinfunction "8_8") (pintype "bidirectional"))
      (node (ref "R11") (pin "1") (pinfunction "1_1") (pintype "passive"))
      (node (ref "SWD") (pin "4") (pinfunction "4_4") (pintype "bidirectional"))
      (node (ref "SWD") (pin "NC1") (pinfunction "P1_NC1") (pintype "bidirectional"))
      (node (ref "SWD") (pin "NC2") (pinfunction "P2_NC2") (pintype "bidirectional"))
      (node (ref "TEST4") (pin "1") (pinfunction "2_1") (pintype "passive"))
      (node (ref "U1") (pin "C") (pinfunction "C_C") (pintype "passive"))
      (node (ref "U2") (pin "C") (pinfunction "C_C") (pintype "passive"))
      (node (ref "USB1") (pin "5") (pinfunction "GND_5") (pintype "bidirectional"))
      (node (ref "USB1") (pin "MNT1") (pinfunction "MTN1_MNT1") (pintype "bidirectional"))
      (node (ref "USB1") (pin "MNT2") (pinfunction "MTN2_MNT2") (pintype "bidirectional"))
      (node (ref "USB1") (pin "MNT3") (pinfunction "MTN3_MNT3") (pintype "bidirectional"))
      (node (ref "USB1") (pin "MNT4") (pinfunction "MTN4_MNT4") (pintype "bidirectional"))
    )
    (net (code "23") (name "MAG_INT") (class "Default")
      (node (ref "IC1") (pin "2") (pinfunction "PC13/RTC_AF1_2") (pintype "bidirectional"))
      (node (ref "IC3") (pin "15") (pinfunction "DRDY_15") (pintype "bidirectional"))
    )
    (net (code "24") (name "MPU_INT") (class "Default")
      (node (ref "IC1") (pin "3") (pinfunction "PC14/OSC32_IN_3") (pintype "bidirectional"))
      (node (ref "IC4") (pin "12") (pinfunction "INT_12") (pintype "bidirectional"))
    )
    (net (code "25") (name "Net-(AUX1-Pad3)") (class "Default")
      (node (ref "AUX1") (pin "3") (pinfunction "3_3") (pintype "bidirectional"))
      (node (ref "D6") (pin "3") (pinfunction "3_3") (pintype "bidirectional"))
      (node (ref "R5") (pin "3") (pinfunction "3_3") (pintype "bidirectional"))
    )
    (net (code "26") (name "Net-(AUX1-Pad4)") (class "Default")
      (node (ref "AUX1") (pin "4") (pinfunction "4_4") (pintype "bidirectional"))
      (node (ref "D6") (pin "1") (pinfunction "1_1") (pintype "bidirectional"))
      (node (ref "R5") (pin "4") (pinfunction "4_4") (pintype "bidirectional"))
    )
    (net (code "27") (name "Net-(AUX2-Pad3)") (class "Default")
      (node (ref "AUX2") (pin "3") (pinfunction "3_3") (pintype "bidirectional"))
      (node (ref "D6") (pin "4") (pinfunction "4_4") (pintype "bidirectional"))
      (node (ref "R5") (pin "2") (pinfunction "2_2") (pintype "bidirectional"))
    )
    (net (code "28") (name "Net-(AUX2-Pad4)") (class "Default")
      (node (ref "AUX2") (pin "4") (pinfunction "4_4") (pintype "bidirectional"))
      (node (ref "D6") (pin "6") (pinfunction "6_6") (pintype "bidirectional"))
      (node (ref "R5") (pin "1") (pinfunction "1_1") (pintype "bidirectional"))
    )
    (net (code "29") (name "Net-(AUX3-Pad3)") (class "Default")
      (node (ref "AUX3") (pin "3") (pinfunction "3_3") (pintype "bidirectional"))
      (node (ref "D4") (pin "6") (pinfunction "6_6") (pintype "bidirectional"))
      (node (ref "R4") (pin "2") (pinfunction "2_2") (pintype "bidirectional"))
    )
    (net (code "30") (name "Net-(AUX3-Pad4)") (class "Default")
      (node (ref "AUX3") (pin "4") (pinfunction "4_4") (pintype "bidirectional"))
      (node (ref "D4") (pin "1") (pinfunction "1_1") (pintype "bidirectional"))
      (node (ref "R4") (pin "1") (pinfunction "1_1") (pintype "bidirectional"))
    )
    (net (code "31") (name "Net-(AUX4-Pad3)") (class "Default")
      (node (ref "AUX4") (pin "3") (pinfunction "3_3") (pintype "bidirectional"))
      (node (ref "D4") (pin "4") (pinfunction "4_4") (pintype "bidirectional"))
      (node (ref "R4") (pin "3") (pinfunction "3_3") (pintype "bidirectional"))
    )
    (net (code "32") (name "Net-(AUX4-Pad4)") (class "Default")
      (node (ref "AUX4") (pin "4") (pinfunction "4_4") (pintype "bidirectional"))
      (node (ref "D4") (pin "3") (pinfunction "3_3") (pintype "bidirectional"))
      (node (ref "R4") (pin "4") (pinfunction "4_4") (pintype "bidirectional"))
    )
    (net (code "33") (name "Net-(D1-A1)") (class "Default")
      (node (ref "D1") (pin "1") (pinfunction "A1_1") (pintype "passive"))
      (node (ref "L3") (pin "2") (pinfunction "2_2") (pintype "passive"))
    )
    (net (code "34") (name "Net-(D1-A2)") (class "Default")
      (node (ref "D1") (pin "2") (pinfunction "A2_2") (pintype "passive"))
      (node (ref "L2") (pin "2") (pinfunction "2_2") (pintype "passive"))
    )
    (net (code "35") (name "Net-(D1-CC)") (class "Default")
      (node (ref "C1") (pin "1") (pinfunction "1_1") (pintype "passive"))
      (node (ref "D1") (pin "3") (pinfunction "CC_3") (pintype "passive"))
      (node (ref "IC6") (pin "1") (pinfunction "IN_1") (pintype "input"))
      (node (ref "IC6") (pin "3") (pinfunction "EN_3") (pintype "input"))
    )
    (net (code "36") (name "Net-(D3-Pad1)") (class "Default")
      (node (ref "D3") (pin "1") (pinfunction "1_1") (pintype "bidirectional"))
      (node (ref "IN") (pin "7") (pinfunction "7_7") (pintype "bidirectional"))
      (node (ref "R3") (pin "7") (pinfunction "7_7") (pintype "bidirectional"))
    )
    (net (code "37") (name "Net-(D3-Pad3)") (class "Default")
      (node (ref "D3") (pin "3") (pinfunction "3_3") (pintype "bidirectional"))
      (node (ref "IN") (pin "8") (pinfunction "8_8") (pintype "bidirectional"))
      (node (ref "R3") (pin "8") (pinfunction "8_8") (pintype "bidirectional"))
    )
    (net (code "38") (name "Net-(D3-Pad4)") (class "Default")
      (node (ref "D3") (pin "4") (pinfunction "4_4") (pintype "bidirectional"))
      (node (ref "IN") (pin "5") (pinfunction "5_5") (pintype "bidirectional"))
      (node (ref "R3") (pin "5") (pinfunction "5_5") (pintype "bidirectional"))
    )
    (net (code "39") (name "Net-(D3-Pad6)") (class "Default")
      (node (ref "D3") (pin "6") (pinfunction "6_6") (pintype "bidirectional"))
      (node (ref "IN") (pin "6") (pinfunction "6_6") (pintype "bidirectional"))
      (node (ref "R3") (pin "6") (pinfunction "6_6") (pintype "bidirectional"))
    )
    (net (code "40") (name "Net-(D5-Pad3)") (class "Default")
      (node (ref "D5") (pin "3") (pinfunction "3_3") (pintype "bidirectional"))
      (node (ref "IN") (pin "4") (pinfunction "4_4") (pintype "bidirectional"))
      (node (ref "R2") (pin "7") (pinfunction "7_7") (pintype "bidirectional"))
    )
    (net (code "41") (name "Net-(D5-Pad4)") (class "Default")
      (node (ref "D5") (pin "4") (pinfunction "4_4") (pintype "bidirectional"))
      (node (ref "IN") (pin "3") (pinfunction "3_3") (pintype "bidirectional"))
      (node (ref "R2") (pin "6") (pinfunction "6_6") (pintype "bidirectional"))
    )
    (net (code "42") (name "Net-(D7-Pad1)") (class "Default")
      (node (ref "D7") (pin "1") (pinfunction "1_1") (pintype "bidirectional"))
      (node (ref "ENGINE8") (pin "3") (pinfunction "3_3") (pintype "passive"))
      (node (ref "R7") (pin "8") (pinfunction "8_8") (pintype "bidirectional"))
    )
    (net (code "43") (name "Net-(D7-Pad3)") (class "Default")
      (node (ref "D7") (pin "3") (pinfunction "3_3") (pintype "bidirectional"))
      (node (ref "ENGINE7") (pin "3") (pinfunction "3_3") (pintype "passive"))
      (node (ref "R7") (pin "7") (pinfunction "7_7") (pintype "bidirectional"))
    )
    (net (code "44") (name "Net-(D7-Pad4)") (class "Default")
      (node (ref "D7") (pin "4") (pinfunction "4_4") (pintype "bidirectional"))
      (node (ref "ENGINE5") (pin "3") (pinfunction "3_3") (pintype "passive"))
      (node (ref "R7") (pin "5") (pinfunction "5_5") (pintype "bidirectional"))
    )
    (net (code "45") (name "Net-(D7-Pad6)") (class "Default")
      (node (ref "D7") (pin "6") (pinfunction "6_6") (pintype "bidirectional"))
      (node (ref "ENGINE6") (pin "3") (pinfunction "3_3") (pintype "passive"))
      (node (ref "R7") (pin "6") (pinfunction "6_6") (pintype "bidirectional"))
    )
    (net (code "46") (name "Net-(D8-Pad1)") (class "Default")
      (node (ref "D8") (pin "1") (pinfunction "1_1") (pintype "bidirectional"))
      (node (ref "ENGINE2") (pin "3") (pinfunction "3_3") (pintype "passive"))
      (node (ref "R6") (pin "6") (pinfunction "6_6") (pintype "bidirectional"))
    )
    (net (code "47") (name "Net-(D8-Pad3)") (class "Default")
      (node (ref "D8") (pin "3") (pinfunction "3_3") (pintype "bidirectional"))
      (node (ref "ENGINE1") (pin "3") (pinfunction "3_3") (pintype "passive"))
      (node (ref "R6") (pin "5") (pinfunction "5_5") (pintype "bidirectional"))
    )
    (net (code "48") (name "Net-(D8-Pad4)") (class "Default")
      (node (ref "D8") (pin "4") (pinfunction "4_4") (pintype "bidirectional"))
      (node (ref "ENGINE3") (pin "3") (pinfunction "3_3") (pintype "passive"))
      (node (ref "R6") (pin "7") (pinfunction "7_7") (pintype "bidirectional"))
    )
    (net (code "49") (name "Net-(D8-Pad6)") (class "Default")
      (node (ref "D8") (pin "6") (pinfunction "6_6") (pintype "bidirectional"))
      (node (ref "ENGINE4") (pin "3") (pinfunction "3_3") (pintype "passive"))
      (node (ref "R6") (pin "8") (pinfunction "8_8") (pintype "bidirectional"))
    )
    (net (code "50") (name "Net-(IC1A-BOOT0)") (class "Default")
      (node (ref "IC1") (pin "60") (pinfunction "BOOT0_60") (pintype "bidirectional"))
      (node (ref "R11") (pin "2") (pinfunction "2_2") (pintype "passive"))
    )
    (net (code "51") (name "Net-(IC1A-PH0{slash}OSC_IN)") (class "Default")
      (node (ref "C21") (pin "2") (pinfunction "2_2") (pintype "passive"))
      (node (ref "IC1") (pin "5") (pinfunction "PH0/OSC_IN_5") (pintype "bidirectional"))
      (node (ref "Q1") (pin "3") (pinfunction "2_3") (pintype "passive"))
    )
    (net (code "52") (name "Net-(IC1A-PH1{slash}OSC_OUT)") (class "Default")
      (node (ref "C20") (pin "2") (pinfunction "2_2") (pintype "passive"))
      (node (ref "IC1") (pin "6") (pinfunction "PH1/OSC_OUT_6") (pintype "bidirectional"))
      (node (ref "Q1") (pin "1") (pinfunction "1_1") (pintype "passive"))
    )
    (net (code "53") (name "Net-(IC1B-PA9{slash}USART1_TX{slash}TIM1_CH2{slash}I2C3_SMBA{slash}OTG_FS_VBUS)") (class "Default")
      (node (ref "IC1") (pin "42") (pinfunction "PA9/USART1_TX/TIM1_CH2/I2C3_SMBA/OTG_FS_VBUS_42") (pintype "bidirectional"))
      (node (ref "R10") (pin "1") (pinfunction "1_1") (pintype "passive"))
    )
    (net (code "54") (name "Net-(IC1D-PC0{slash}ADC123_IN10)") (class "Default")
      (node (ref "IC1") (pin "8") (pinfunction "PC0/ADC123_IN10_8") (pintype "bidirectional"))
      (node (ref "R1") (pin "4") (pinfunction "4_4") (pintype "bidirectional"))
    )
    (net (code "55") (name "Net-(IC1D-PC1{slash}ADC123_IN11)") (class "Default")
      (node (ref "IC1") (pin "9") (pinfunction "PC1/ADC123_IN11_9") (pintype "bidirectional"))
      (node (ref "R1") (pin "3") (pinfunction "3_3") (pintype "bidirectional"))
    )
    (net (code "56") (name "Net-(IC1E-VCAP1)") (class "Default")
      (node (ref "C22") (pin "1") (pinfunction "1_1") (pintype "passive"))
      (node (ref "IC1") (pin "31") (pinfunction "VCAP1_31") (pintype "bidirectional"))
    )
    (net (code "57") (name "Net-(IC1E-VCAP2)") (class "Default")
      (node (ref "C23") (pin "1") (pinfunction "1_1") (pintype "passive"))
      (node (ref "IC1") (pin "47") (pinfunction "VCAP2_47") (pintype "bidirectional"))
    )
    (net (code "58") (name "Net-(IC3-C1)") (class "Default")
      (node (ref "C25") (pin "1") (pinfunction "1_1") (pintype "passive"))
      (node (ref "IC3") (pin "10") (pinfunction "C1_10") (pintype "bidirectional"))
    )
    (net (code "59") (name "Net-(IC3-SETC)") (class "Default")
      (node (ref "C26") (pin "2") (pinfunction "2_2") (pintype "passive"))
      (node (ref "IC3") (pin "12") (pinfunction "SETC_12") (pintype "bidirectional"))
    )
    (net (code "60") (name "Net-(IC3-SETP)") (class "Default")
      (node (ref "C26") (pin "1") (pinfunction "1_1") (pintype "passive"))
      (node (ref "IC3") (pin "8") (pinfunction "SETP_8") (pintype "bidirectional"))
    )
    (net (code "61") (name "Net-(IC4-CPOUT)") (class "Default")
      (node (ref "C24") (pin "1") (pinfunction "1_1") (pintype "passive"))
      (node (ref "IC4") (pin "20") (pinfunction "CPOUT_20") (pintype "bidirectional"))
    )
    (net (code "62") (name "Net-(IC4-REGOUT)") (class "Default")
      (node (ref "C18") (pin "1") (pinfunction "1_1") (pintype "passive"))
      (node (ref "IC4") (pin "10") (pinfunction "REGOUT_10") (pintype "bidirectional"))
    )
    (net (code "63") (name "Net-(MMCX1-SIGNAL)") (class "Default")
      (node (ref "MMCX1") (pin "S") (pinfunction "SIGNAL_S") (pintype "bidirectional"))
      (node (ref "MODULE1") (pin "1") (pinfunction "ANT_1") (pintype "bidirectional"))
    )
    (net (code "64") (name "Net-(MODULE1-GPIO0)") (class "Default")
      (node (ref "MODULE1") (pin "4") (pinfunction "TXANT_4") (pintype "input"))
      (node (ref "MODULE1") (pin "6") (pinfunction "GPIO0_6") (pintype "bidirectional"))
    )
    (net (code "65") (name "Net-(MODULE1-GPIO1)") (class "Default")
      (node (ref "MODULE1") (pin "3") (pinfunction "RXANT_3") (pintype "input"))
      (node (ref "MODULE1") (pin "7") (pinfunction "GPIO1_7") (pintype "bidirectional"))
    )
    (net (code "66") (name "Net-(PWR-PadA)") (class "Default")
      (node (ref "PWR") (pin "A") (pinfunction "A_A") (pintype "passive"))
      (node (ref "R2") (pin "5") (pinfunction "5_5") (pintype "bidirectional"))
    )
    (net (code "67") (name "Net-(R1-Pad5)") (class "Default")
      (node (ref "R1") (pin "5") (pinfunction "5_5") (pintype "bidirectional"))
      (node (ref "U2") (pin "A") (pinfunction "A_A") (pintype "passive"))
    )
    (net (code "68") (name "Net-(R1-Pad6)") (class "Default")
      (node (ref "R1") (pin "6") (pinfunction "6_6") (pintype "bidirectional"))
      (node (ref "U1") (pin "A") (pinfunction "A_A") (pintype "passive"))
    )
    (net (code "69") (name "Net-(USB1-D+)") (class "Default")
      (node (ref "D2") (pin "6") (pinfunction "6_6") (pintype "bidirectional"))
      (node (ref "R8") (pin "2") (pinfunction "2_2") (pintype "passive"))
      (node (ref "USB1") (pin "3") (pinfunction "D+_3") (pintype "bidirectional"))
    )
    (net (code "70") (name "Net-(USB1-D-)") (class "Default")
      (node (ref "D2") (pin "1") (pinfunction "1_1") (pintype "bidirectional"))
      (node (ref "R9") (pin "2") (pinfunction "2_2") (pintype "passive"))
      (node (ref "USB1") (pin "2") (pinfunction "D-_2") (pintype "bidirectional"))
    )
    (net (code "71") (name "RF_IRQ") (class "Default")
      (node (ref "IC1") (pin "4") (pinfunction "PC15/OSC32_OUT_4") (pintype "bidirectional"))
      (node (ref "MODULE1") (pin "14") (pinfunction "NIRQ_14") (pintype "output"))
    )
    (net (code "72") (name "RF_MISO") (class "Default")
      (node (ref "IC1") (pin "22") (pinfunction "PA6/SPI1_MISO/TIM13_CH1/TIM3_CH1/ADC12_IN6_22") (pintype "bidirectional"))
      (node (ref "IC5") (pin "2") (pinfunction "MISO_2") (pintype "bidirectional"))
      (node (ref "MODULE1") (pin "10") (pinfunction "SDO_10") (pintype "output"))
    )
    (net (code "73") (name "RF_MOSI") (class "Default")
      (node (ref "IC1") (pin "23") (pinfunction "PA7/SPI1_MOSI/TIM14_CH1/TIM3_CH2/ADC12_IN7_23") (pintype "bidirectional"))
      (node (ref "IC5") (pin "5") (pinfunction "MOSI_5") (pintype "bidirectional"))
      (node (ref "MODULE1") (pin "11") (pinfunction "SDI_11") (pintype "input"))
    )
    (net (code "74") (name "RF_SCLK") (class "Default")
      (node (ref "IC1") (pin "21") (pinfunction "PA5/SPI1_SCK/ADC12_IN5/DAC2_OUT_21") (pintype "bidirectional"))
      (node (ref "IC5") (pin "6") (pinfunction "SCK_6") (pintype "bidirectional"))
      (node (ref "MODULE1") (pin "12") (pinfunction "SCLK_12") (pintype "input"))
    )
    (net (code "75") (name "RF_SEL") (class "Default")
      (node (ref "IC1") (pin "20") (pinfunction "PA4/SPI1_NSS/SPI3_NSS/ADC12_IN4/DAC1_OUT_20") (pintype "bidirectional"))
      (node (ref "MODULE1") (pin "13") (pinfunction "NSEL_13") (pintype "input"))
    )
    (net (code "76") (name "RXD3") (class "Default")
      (node (ref "IC1") (pin "52") (pinfunction "PC11/SPI3_MISO/UART4_RX/USART3_RX_52") (pintype "bidirectional"))
      (node (ref "R5") (pin "5") (pinfunction "5_5") (pintype "bidirectional"))
    )
    (net (code "77") (name "RXD4") (class "Default")
      (node (ref "IC1") (pin "15") (pinfunction "PA1/USART4_RX/TIM5_CH2/TIM2_CH2/ADC123_IN1_15") (pintype "bidirectional"))
      (node (ref "R4") (pin "8") (pinfunction "8_8") (pintype "bidirectional"))
    )
    (net (code "78") (name "RXD5") (class "Default")
      (node (ref "IC1") (pin "54") (pinfunction "PD2/UART5_RX_54") (pintype "bidirectional"))
      (node (ref "R5") (pin "8") (pinfunction "8_8") (pintype "bidirectional"))
    )
    (net (code "79") (name "SCL") (class "Default")
      (node (ref "IC1") (pin "29") (pinfunction "PB10/SPI2_SCK/I2C2_SCL/USART3_TX/TIM2_CH3_29") (pintype "bidirectional"))
      (node (ref "IC2") (pin "8") (pinfunction "SCLK_8") (pintype "bidirectional"))
      (node (ref "IC3") (pin "1") (pinfunction "SCL/SCLK_1") (pintype "bidirectional"))
      (node (ref "IC4") (pin "23") (pinfunction "SCL_23") (pintype "bidirectional"))
      (node (ref "R13") (pin "2") (pinfunction "2_2") (pintype "passive"))
      (node (ref "TEST2") (pin "1") (pinfunction "2_1") (pintype "passive"))
    )
    (net (code "80") (name "SDA") (class "Default")
      (node (ref "IC1") (pin "30") (pinfunction "PB11/I2C2_SDA/USART3_RX/TIM2_CH4_30") (pintype "bidirectional"))
      (node (ref "IC2") (pin "7") (pinfunction "SDA/SDI_7") (pintype "bidirectional"))
      (node (ref "IC3") (pin "16") (pinfunction "SDA/MOSI_16") (pintype "bidirectional"))
      (node (ref "IC4") (pin "24") (pinfunction "SDA_24") (pintype "bidirectional"))
      (node (ref "R14") (pin "2") (pinfunction "2_2") (pintype "passive"))
      (node (ref "TEST1") (pin "1") (pinfunction "2_1") (pintype "passive"))
    )
    (net (code "81") (name "SWCLK") (class "Default")
      (node (ref "IC1") (pin "49") (pinfunction "PA14/JTCK-SWCLK_49") (pintype "bidirectional"))
      (node (ref "SWD") (pin "1") (pinfunction "1_1") (pintype "bidirectional"))
    )
    (net (code "82") (name "SWDIO") (class "Default")
      (node (ref "IC1") (pin "46") (pinfunction "PA13/JTMS-SWDIO_46") (pintype "bidirectional"))
      (node (ref "SWD") (pin "2") (pinfunction "2_2") (pintype "bidirectional"))
    )
    (net (code "83") (name "TXD3") (class "Default")
      (node (ref "IC1") (pin "51") (pinfunction "PC10/SPI3_SCK/UART4_TX/USART3_TX_51") (pintype "bidirectional"))
      (node (ref "R5") (pin "6") (pinfunction "6_6") (pintype "bidirectional"))
    )
    (net (code "84") (name "TXD4") (class "Default")
      (node (ref "IC1") (pin "14") (pinfunction "PA0/USART4_TX/TIM5_CH1/ADC123_IN0/WKUP_14") (pintype "bidirectional"))
      (node (ref "R4") (pin "7") (pinfunction "7_7") (pintype "bidirectional"))
    )
    (net (code "85") (name "TXD5") (class "Default")
      (node (ref "IC1") (pin "53") (pinfunction "PC12/UART5_TX/SPI3_MOSI_53") (pintype "bidirectional"))
      (node (ref "R5") (pin "7") (pinfunction "7_7") (pintype "bidirectional"))
    )
    (net (code "86") (name "VCC") (class "Default")
      (node (ref "D2") (pin "2") (pinfunction "2_2") (pintype "bidirectional"))
      (node (ref "L2") (pin "1") (pinfunction "1_1") (pintype "passive"))
      (node (ref "R10") (pin "2") (pinfunction "2_2") (pintype "passive"))
      (node (ref "USB1") (pin "1") (pinfunction "VBUS_1") (pintype "bidirectional"))
    )
    (net (code "87") (name "VCCA") (class "Default")
      (node (ref "C13") (pin "1") (pinfunction "1_1") (pintype "passive"))
      (node (ref "C14") (pin "1") (pinfunction "1_1") (pintype "passive"))
      (node (ref "C15") (pin "1") (pinfunction "1_1") (pintype "passive"))
      (node (ref "C2") (pin "1") (pinfunction "1_1") (pintype "passive"))
      (node (ref "IC2") (pin "1") (pinfunction "VCC_1") (pintype "bidirectional"))
      (node (ref "IC2") (pin "2") (pinfunction "PS_2") (pintype "bidirectional"))
      (node (ref "IC3") (pin "13") (pinfunction "VDDIO_13") (pintype "bidirectional"))
      (node (ref "IC3") (pin "2") (pinfunction "VDD_2") (pintype "bidirectional"))
      (node (ref "IC3") (pin "4") (pinfunction "~{CS}_4") (pintype "bidirectional"))
      (node (ref "IC3") (pin "6") (pinfunction "I2C/~{SPI}_6") (pintype "bidirectional"))
      (node (ref "IC4") (pin "13") (pinfunction "VDD_13") (pintype "bidirectional"))
      (node (ref "IC4") (pin "8") (pinfunction "VLOGIC_8") (pintype "bidirectional"))
      (node (ref "IC4") (pin "9") (pinfunction "AD0_9") (pintype "bidirectional"))
      (node (ref "L1") (pin "2") (pinfunction "2_2") (pintype "passive"))
    )
    (net (code "88") (name "unconnected-(D2-Pad3)") (class "Default")
      (node (ref "D2") (pin "3") (pinfunction "3_3") (pintype "bidirectional"))
    )
    (net (code "89") (name "unconnected-(D2-Pad4)") (class "Default")
      (node (ref "D2") (pin "4") (pinfunction "4_4") (pintype "bidirectional"))
    )
    (net (code "90") (name "unconnected-(D3-Pad2)") (class "Default")
      (node (ref "D3") (pin "2") (pinfunction "2_2") (pintype "bidirectional"))
    )
    (net (code "91") (name "unconnected-(D4-Pad2)") (class "Default")
      (node (ref "D4") (pin "2") (pinfunction "2_2") (pintype "bidirectional"))
    )
    (net (code "92") (name "unconnected-(D5-Pad1)") (class "Default")
      (node (ref "D5") (pin "1") (pinfunction "1_1") (pintype "bidirectional"))
    )
    (net (code "93") (name "unconnected-(D5-Pad2)") (class "Default")
      (node (ref "D5") (pin "2") (pinfunction "2_2") (pintype "bidirectional"))
    )
    (net (code "94") (name "unconnected-(D5-Pad6)") (class "Default")
      (node (ref "D5") (pin "6") (pinfunction "6_6") (pintype "bidirectional"))
    )
    (net (code "95") (name "unconnected-(D6-Pad2)") (class "Default")
      (node (ref "D6") (pin "2") (pinfunction "2_2") (pintype "bidirectional"))
    )
    (net (code "96") (name "unconnected-(D7-Pad2)") (class "Default")
      (node (ref "D7") (pin "2") (pinfunction "2_2") (pintype "bidirectional"))
    )
    (net (code "97") (name "unconnected-(D8-Pad2)") (class "Default")
      (node (ref "D8") (pin "2") (pinfunction "2_2") (pintype "bidirectional"))
    )
    (net (code "98") (name "unconnected-(IC1B-PA8{slash}TIM1_CH1{slash}I2C3_SCL-Pad41)") (class "Default")
      (node (ref "IC1") (pin "41") (pinfunction "PA8/TIM1_CH1/I2C3_SCL_41") (pintype "bidirectional"))
    )
    (net (code "99") (name "unconnected-(IC1B-PA10{slash}USART1_RX{slash}TIM1_CH3{slash}OTG_FS_ID-Pad43)") (class "Default")
      (node (ref "IC1") (pin "43") (pinfunction "PA10/USART1_RX/TIM1_CH3/OTG_FS_ID_43") (pintype "bidirectional"))
    )
    (net (code "100") (name "unconnected-(IC1B-PA15{slash}JTDI{slash}SPI3_NSS{slash}I2S3_WS{slash}SPI1_NSS-Pad50)") (class "Default")
      (node (ref "IC1") (pin "50") (pinfunction "PA15/JTDI/SPI3_NSS/I2S3_WS/SPI1_NSS_50") (pintype "bidirectional"))
    )
    (net (code "101") (name "unconnected-(IC1C-PB2{slash}BOOT1-Pad28)") (class "Default")
      (node (ref "IC1") (pin "28") (pinfunction "PB2/BOOT1_28") (pintype "bidirectional"))
    )
    (net (code "102") (name "unconnected-(IC1C-PB3{slash}JTDO{slash}SPI3_SCK{slash}TIM2_CH2{slash}SPI1_SCK-Pad55)") (class "Default")
      (node (ref "IC1") (pin "55") (pinfunction "PB3/JTDO/SPI3_SCK/TIM2_CH2/SPI1_SCK_55") (pintype "bidirectional"))
    )
    (net (code "103") (name "unconnected-(IC1C-PB4{slash}~{NJTRST}{slash}SPI3_MISO{slash}TIM3_CH1{slash}SPI1_MISO-Pad56)") (class "Default")
      (node (ref "IC1") (pin "56") (pinfunction "PB4/~{NJTRST}/SPI3_MISO/TIM3_CH1/SPI1_MISO_56") (pintype "bidirectional"))
    )
    (net (code "104") (name "unconnected-(IC1C-PB5{slash}I2C1_SMBA{slash}CAN2_RX{slash}TIM3_CH2{slash}SPI1_MOSI{slash}SPI3_MOSI-Pad57)") (class "Default")
      (node (ref "IC1") (pin "57") (pinfunction "PB5/I2C1_SMBA/CAN2_RX/TIM3_CH2/SPI1_MOSI/SPI3_MOSI_57") (pintype "bidirectional"))
    )
    (net (code "105") (name "unconnected-(IC1D-PC2{slash}SPI2_MISO{slash}ADC123_IN12-Pad10)") (class "Default")
      (node (ref "IC1") (pin "10") (pinfunction "PC2/SPI2_MISO/ADC123_IN12_10") (pintype "bidirectional"))
    )
    (net (code "106") (name "unconnected-(IC1D-PC3{slash}SPI2_MOSI{slash}ADC123_IN13-Pad11)") (class "Default")
      (node (ref "IC1") (pin "11") (pinfunction "PC3/SPI2_MOSI/ADC123_IN13_11") (pintype "bidirectional"))
    )
    (net (code "107") (name "unconnected-(IC1D-PC5{slash}ADC12_IN15-Pad25)") (class "Default")
      (node (ref "IC1") (pin "25") (pinfunction "PC5/ADC12_IN15_25") (pintype "bidirectional"))
    )
    (net (code "108") (name "unconnected-(IC2-SDO-Pad6)") (class "Default")
      (node (ref "IC2") (pin "6") (pinfunction "SDO_6") (pintype "bidirectional"))
    )
    (net (code "109") (name "unconnected-(IC3-MISO-Pad5)") (class "Default")
      (node (ref "IC3") (pin "5") (pinfunction "MISO_5") (pintype "bidirectional"))
    )
    (net (code "110") (name "unconnected-(IC4-AUX_CLK-Pad7)") (class "Default")
      (node (ref "IC4") (pin "7") (pinfunction "AUX_CLK_7") (pintype "bidirectional"))
    )
    (net (code "111") (name "unconnected-(IC4-AUX_DA-Pad6)") (class "Default")
      (node (ref "IC4") (pin "6") (pinfunction "AUX_DA_6") (pintype "bidirectional"))
    )
    (net (code "112") (name "unconnected-(IC4-CLKIN-Pad1)") (class "Default")
      (node (ref "IC4") (pin "1") (pinfunction "CLKIN_1") (pintype "bidirectional"))
    )
    (net (code "113") (name "unconnected-(IC4-CLKOUT-Pad22)") (class "Default")
      (node (ref "IC4") (pin "22") (pinfunction "CLKOUT_22") (pintype "bidirectional"))
    )
    (net (code "114") (name "unconnected-(IC4-FSYNC-Pad11)") (class "Default")
      (node (ref "IC4") (pin "11") (pinfunction "FSYNC_11") (pintype "bidirectional"))
    )
    (net (code "115") (name "unconnected-(IC4-RESV-Pad19)") (class "Default")
      (node (ref "IC4") (pin "19") (pinfunction "RESV_19") (pintype "bidirectional"))
    )
    (net (code "116") (name "unconnected-(IC4-RESV-Pad21)") (class "Default")
      (node (ref "IC4") (pin "21") (pinfunction "RESV_21") (pintype "bidirectional"))
    )
    (net (code "117") (name "unconnected-(IC6-BP-Pad4)") (class "Default")
      (node (ref "IC6") (pin "4") (pinfunction "BP_4") (pintype "input"))
    )
    (net (code "118") (name "unconnected-(MODULE1-GPIO2-Pad8)") (class "Default")
      (node (ref "MODULE1") (pin "8") (pinfunction "GPIO2_8") (pintype "bidirectional"))
    )
    (net (code "119") (name "unconnected-(USB1-ID-Pad4)") (class "Default")
      (node (ref "USB1") (pin "4") (pinfunction "ID_4") (pintype "bidirectional"))
    )
    (net (code "120") (name "~{SRST}") (class "Default")
      (node (ref "C19") (pin "1") (pinfunction "1_1") (pintype "passive"))
      (node (ref "IC1") (pin "7") (pinfunction "~{NRST}_7") (pintype "bidirectional"))
      (node (ref "R12") (pin "2") (pinfunction "2_2") (pintype "passive"))
      (node (ref "SWD") (pin "3") (pinfunction "3_3") (pintype "bidirectional"))
    )
  )
)
